# utilidong-lipo-charger_septic-sepic-mk-1.net
KiCad netlist of a schematic drawn in EAGLE
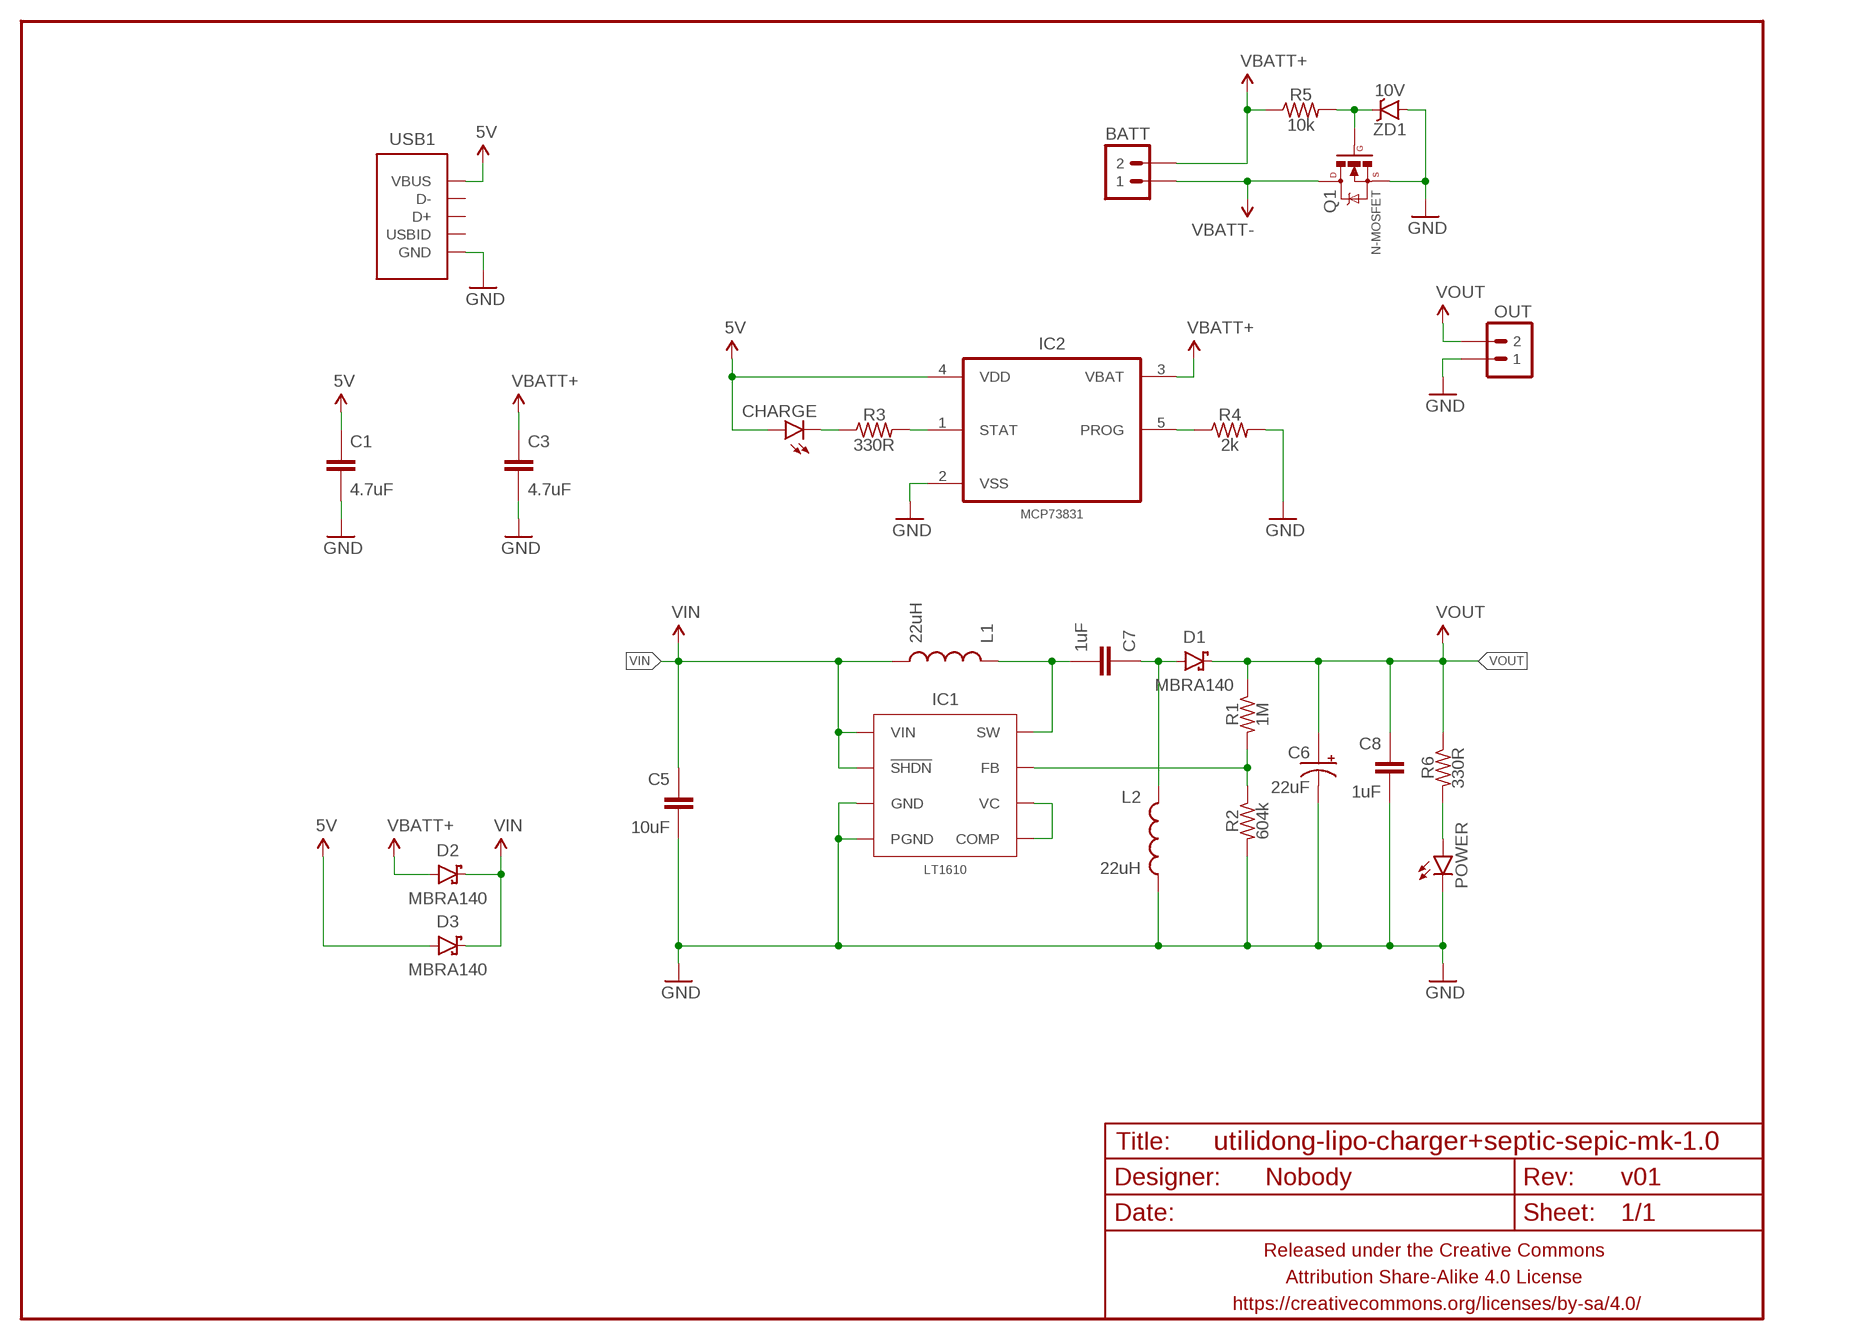
[diagram p0: schematic, sheet 1]

(export (version "E")
  (design (tool "Eeschema 10.0.6"))
  (components
    (comp (ref "BATT")
      (value "M02PTH-CENTERED-R+")
      (footprint "eagle-import:1X02-CENTER-R+")
      (libsource (lib "eagle-import") (part "M02PTH-CENTERED-R+"))
    )
    (comp (ref "C1")
      (value "4.7uF")
      (footprint "eagle-import:C0805")
      (libsource (lib "eagle-import") (part "CAPACITOR-CERAMICC0805"))
    )
    (comp (ref "C3")
      (value "4.7uF")
      (footprint "eagle-import:C0805")
      (libsource (lib "eagle-import") (part "CAPACITOR-CERAMICC0805"))
    )
    (comp (ref "C5")
      (value "10uF")
      (footprint "eagle-import:C0805")
      (libsource (lib "eagle-import") (part "CAPACITOR-CERAMICC0805"))
    )
    (comp (ref "C6")
      (value "22uF")
      (footprint "eagle-import:E2,5-6")
      (libsource (lib "eagle-import") (part "CAPACITOR-POLARIZEDE2.5-6"))
    )
    (comp (ref "C7")
      (value "1uF")
      (footprint "eagle-import:C0805")
      (libsource (lib "eagle-import") (part "CAPACITOR-CERAMICC0805"))
    )
    (comp (ref "C8")
      (value "1uF")
      (footprint "eagle-import:C0805")
      (libsource (lib "eagle-import") (part "CAPACITOR-CERAMICC0805"))
    )
    (comp (ref "CHARGE")
      (value "LED1206")
      (footprint "eagle-import:LED-1206")
      (libsource (lib "eagle-import") (part "LED1206"))
    )
    (comp (ref "D1")
      (value "MBRA140")
      (footprint "eagle-import:SMA-DIODE-SCHOTTKY")
      (libsource (lib "eagle-import") (part "DIODE-SCHOTTKYSMA"))
    )
    (comp (ref "D2")
      (value "MBRA140")
      (footprint "eagle-import:SMA-DIODE")
      (libsource (lib "eagle-import") (part "DIODE-SCHOTTKYMBRA140"))
    )
    (comp (ref "D3")
      (value "MBRA140")
      (footprint "eagle-import:SMA-DIODE")
      (libsource (lib "eagle-import") (part "DIODE-SCHOTTKYMBRA140"))
    )
    (comp (ref "FRAME1")
      (value "FRAME-LETTERNO_PACKAGE")
      (footprint "eagle-import:DUMMY")
      (fields (field (name "DESIGNER") "Nobody"))
      (libsource (lib "eagle-import") (part "FRAME-LETTERNO_PACKAGE"))
    )
    (comp (ref "IC1")
      (value "LT1610")
      (footprint "eagle-import:SO08")
      (libsource (lib "eagle-import") (part "LT1610SOICN8"))
    )
    (comp (ref "IC2")
      (value "MCP73831")
      (footprint "eagle-import:SOT95P280X145-5N")
      (fields (field (name "MPN") "MCP73831T-2ACI/OT"))
      (libsource (lib "eagle-import") (part "MCP73831T-2ACI/OT"))
    )
    (comp (ref "L1")
      (value "22uH")
      (footprint "eagle-import:TAIYO-YUDEN-40XX")
      (libsource (lib "eagle-import") (part "INDUCTORTAIYO-YUDEN-40XX"))
    )
    (comp (ref "L2")
      (value "22uH")
      (footprint "eagle-import:TAIYO-YUDEN-40XX")
      (libsource (lib "eagle-import") (part "INDUCTORTAIYO-YUDEN-40XX"))
    )
    (comp (ref "OUT")
      (value "M02PTH-CENTERED-R+")
      (footprint "eagle-import:1X02-CENTER-R+")
      (libsource (lib "eagle-import") (part "M02PTH-CENTERED-R+"))
    )
    (comp (ref "POWER")
      (value "LED1206")
      (footprint "eagle-import:LED-1206")
      (libsource (lib "eagle-import") (part "LED1206"))
    )
    (comp (ref "Q1")
      (value "N-MOSFET")
      (footprint "eagle-import:SOT23")
      (libsource (lib "eagle-import") (part "MOSFET-NCHANNELBSS138"))
    )
    (comp (ref "R1")
      (value "1M")
      (footprint "eagle-import:R0805")
      (libsource (lib "eagle-import") (part "RESISTORR0805"))
    )
    (comp (ref "R2")
      (value "604k")
      (footprint "eagle-import:R0805")
      (libsource (lib "eagle-import") (part "RESISTORR0805"))
    )
    (comp (ref "R3")
      (value "330R")
      (footprint "eagle-import:R0805")
      (libsource (lib "eagle-import") (part "RESISTORR0805"))
    )
    (comp (ref "R4")
      (value "2k")
      (footprint "eagle-import:R0805")
      (libsource (lib "eagle-import") (part "RESISTORR0805"))
    )
    (comp (ref "R5")
      (value "10k")
      (footprint "eagle-import:R0805")
      (libsource (lib "eagle-import") (part "RESISTORR0805"))
    )
    (comp (ref "R6")
      (value "330R")
      (footprint "eagle-import:R0805")
      (libsource (lib "eagle-import") (part "RESISTORR0805"))
    )
    (comp (ref "USB1")
      (value "USB-ABCOMBO")
      (footprint "eagle-import:USB-MICRO-B-FCI-CUTOUT")
      (libsource (lib "eagle-import") (part "USB-ABCOMBO"))
    )
    (comp (ref "ZD1")
      (value "10V")
      (footprint "eagle-import:SOD123-ZENER")
      (libsource (lib "eagle-import") (part "DIODE-ZENERSOD123"))
    )
  )
  (nets
    (net (code "1") (name "5V") (class "Default")
      (node (ref "C1") (pin "1") (pinfunction "1_1") (pintype "passive"))
      (node (ref "CHARGE") (pin "A") (pinfunction "A_A") (pintype "passive"))
      (node (ref "D3") (pin "A") (pinfunction "A_A") (pintype "passive"))
      (node (ref "IC2") (pin "4") (pinfunction "VDD_4") (pintype "power_in"))
      (node (ref "USB1") (pin "1") (pinfunction "VBUS_1") (pintype "bidirectional"))
    )
    (net (code "2") (name "GND") (class "Default")
      (node (ref "C1") (pin "2") (pinfunction "2_2") (pintype "passive"))
      (node (ref "C3") (pin "2") (pinfunction "2_2") (pintype "passive"))
      (node (ref "C5") (pin "2") (pinfunction "2_2") (pintype "passive"))
      (node (ref "C6") (pin "-") (pinfunction "-_-") (pintype "passive"))
      (node (ref "C8") (pin "2") (pinfunction "2_2") (pintype "passive"))
      (node (ref "IC1") (pin "4") (pinfunction "PGND_4") (pintype "passive"))
      (node (ref "IC1") (pin "7") (pinfunction "GND_7") (pintype "passive"))
      (node (ref "IC2") (pin "2") (pinfunction "VSS_2") (pintype "power_in"))
      (node (ref "L2") (pin "2") (pinfunction "2_2") (pintype "passive"))
      (node (ref "OUT") (pin "1") (pinfunction "1_1") (pintype "passive"))
      (node (ref "POWER") (pin "C") (pinfunction "C_C") (pintype "passive"))
      (node (ref "Q1") (pin "2") (pinfunction "S_2") (pintype "passive"))
      (node (ref "R2") (pin "2") (pinfunction "2_2") (pintype "passive"))
      (node (ref "R4") (pin "2") (pinfunction "2_2") (pintype "passive"))
      (node (ref "USB1") (pin "5") (pinfunction "GND_5") (pintype "bidirectional"))
      (node (ref "USB1") (pin "P$1") (pinfunction "GND_P$1") (pintype "bidirectional"))
      (node (ref "USB1") (pin "P$2") (pinfunction "GND_P$2") (pintype "bidirectional"))
      (node (ref "ZD1") (pin "A") (pinfunction "A_A") (pintype "passive"))
    )
    (net (code "3") (name "Net-(C7-Pad1)") (class "Default")
      (node (ref "C7") (pin "1") (pinfunction "1_1") (pintype "passive"))
      (node (ref "D1") (pin "A") (pinfunction "A_A") (pintype "passive"))
      (node (ref "L2") (pin "1") (pinfunction "1_1") (pintype "passive"))
    )
    (net (code "4") (name "Net-(CHARGE-PadC)") (class "Default")
      (node (ref "CHARGE") (pin "C") (pinfunction "C_C") (pintype "passive"))
      (node (ref "R3") (pin "1") (pinfunction "1_1") (pintype "passive"))
    )
    (net (code "5") (name "Net-(IC1-COMP)") (class "Default")
      (node (ref "IC1") (pin "1") (pinfunction "VC_1") (pintype "passive"))
      (node (ref "IC1") (pin "8") (pinfunction "COMP_8") (pintype "passive"))
    )
    (net (code "6") (name "Net-(IC1-FB)") (class "Default")
      (node (ref "IC1") (pin "2") (pinfunction "FB_2") (pintype "passive"))
      (node (ref "R1") (pin "2") (pinfunction "2_2") (pintype "passive"))
      (node (ref "R2") (pin "1") (pinfunction "1_1") (pintype "passive"))
    )
    (net (code "7") (name "Net-(IC1-SW)") (class "Default")
      (node (ref "C7") (pin "2") (pinfunction "2_2") (pintype "passive"))
      (node (ref "IC1") (pin "5") (pinfunction "SW_5") (pintype "passive"))
      (node (ref "L1") (pin "1") (pinfunction "1_1") (pintype "passive"))
    )
    (net (code "8") (name "Net-(IC2-PROG)") (class "Default")
      (node (ref "IC2") (pin "5") (pinfunction "PROG_5") (pintype "input"))
      (node (ref "R4") (pin "1") (pinfunction "1_1") (pintype "passive"))
    )
    (net (code "9") (name "Net-(IC2-STAT)") (class "Default")
      (node (ref "IC2") (pin "1") (pinfunction "STAT_1") (pintype "output"))
      (node (ref "R3") (pin "2") (pinfunction "2_2") (pintype "passive"))
    )
    (net (code "10") (name "Net-(POWER-PadA)") (class "Default")
      (node (ref "POWER") (pin "A") (pinfunction "A_A") (pintype "passive"))
      (node (ref "R6") (pin "2") (pinfunction "2_2") (pintype "passive"))
    )
    (net (code "11") (name "Net-(Q1-G)") (class "Default")
      (node (ref "Q1") (pin "1") (pinfunction "G_1") (pintype "passive"))
      (node (ref "R5") (pin "2") (pinfunction "2_2") (pintype "passive"))
      (node (ref "ZD1") (pin "C") (pinfunction "C_C") (pintype "passive"))
    )
    (net (code "12") (name "VBATT+") (class "Default")
      (node (ref "BATT") (pin "2") (pinfunction "2_2") (pintype "passive"))
      (node (ref "C3") (pin "1") (pinfunction "1_1") (pintype "passive"))
      (node (ref "D2") (pin "A") (pinfunction "A_A") (pintype "passive"))
      (node (ref "IC2") (pin "3") (pinfunction "VBAT_3") (pintype "output"))
      (node (ref "R5") (pin "1") (pinfunction "1_1") (pintype "passive"))
    )
    (net (code "13") (name "VBATT-") (class "Default")
      (node (ref "BATT") (pin "1") (pinfunction "1_1") (pintype "passive"))
      (node (ref "Q1") (pin "3") (pinfunction "D_3") (pintype "passive"))
    )
    (net (code "14") (name "VIN") (class "Default")
      (node (ref "C5") (pin "1") (pinfunction "1_1") (pintype "passive"))
      (node (ref "D2") (pin "C") (pinfunction "C_C") (pintype "passive"))
      (node (ref "D3") (pin "C") (pinfunction "C_C") (pintype "passive"))
      (node (ref "IC1") (pin "3") (pinfunction "~{SHDN}_3") (pintype "passive"))
      (node (ref "IC1") (pin "6") (pinfunction "VIN_6") (pintype "passive"))
      (node (ref "L1") (pin "2") (pinfunction "2_2") (pintype "passive"))
    )
    (net (code "15") (name "VOUT") (class "Default")
      (node (ref "C6") (pin "+") (pinfunction "+_+") (pintype "passive"))
      (node (ref "C8") (pin "1") (pinfunction "1_1") (pintype "passive"))
      (node (ref "D1") (pin "C") (pinfunction "C_C") (pintype "passive"))
      (node (ref "OUT") (pin "2") (pinfunction "2_2") (pintype "passive"))
      (node (ref "R1") (pin "1") (pinfunction "1_1") (pintype "passive"))
      (node (ref "R6") (pin "1") (pinfunction "1_1") (pintype "passive"))
    )
    (net (code "16") (name "unconnected-(USB1-D+-Pad3)") (class "Default")
      (node (ref "USB1") (pin "3") (pinfunction "D+_3") (pintype "bidirectional"))
    )
    (net (code "17") (name "unconnected-(USB1-D--Pad2)") (class "Default")
      (node (ref "USB1") (pin "2") (pinfunction "D-_2") (pintype "bidirectional"))
    )
    (net (code "18") (name "unconnected-(USB1-USBID-Pad4)") (class "Default")
      (node (ref "USB1") (pin "4") (pinfunction "USBID_4") (pintype "bidirectional"))
    )
  )
)
